# Sheet1.net
KiCad netlist of a schematic drawn in Altium Designer
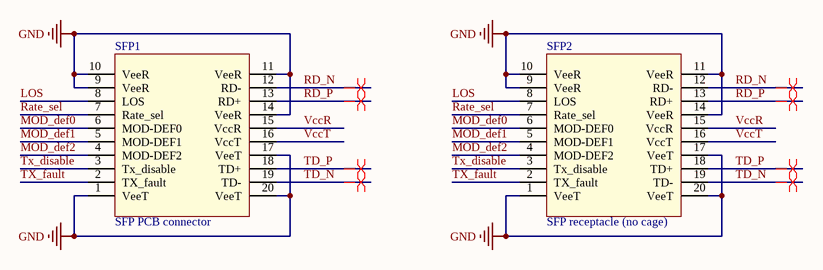
[diagram p0: Sheet1.SchDoc]

(export (version "E")
  (design (tool "Eeschema 10.0.6"))
  (components
    (comp (ref "SFP1")
      (value "SFP PCB connector")
      (footprint "SFP pcb con solder")
      (libsource (lib "SFPextension") (part "SFP PCB connector"))
    )
    (comp (ref "SFP2")
      (value "SFP receptacle (no cage)")
      (footprint "SFP receptacle (no cage)")
      (libsource (lib "SFPextension") (part "SFP receptacle (no cage)"))
    )
  )
  (nets
    (net (code "1") (name "/LOS") (class "Default")
      (node (ref "SFP1") (pin "8") (pinfunction "LOS_8") (pintype "power_in"))
      (node (ref "SFP2") (pin "8") (pinfunction "LOS_8") (pintype "power_in"))
    )
    (net (code "2") (name "/MOD_def0") (class "Default")
      (node (ref "SFP1") (pin "6") (pinfunction "MOD-DEF0_6") (pintype "power_in"))
      (node (ref "SFP2") (pin "6") (pinfunction "MOD-DEF0_6") (pintype "power_in"))
    )
    (net (code "3") (name "/MOD_def1") (class "Default")
      (node (ref "SFP1") (pin "5") (pinfunction "MOD-DEF1_5") (pintype "power_in"))
      (node (ref "SFP2") (pin "5") (pinfunction "MOD-DEF1_5") (pintype "power_in"))
    )
    (net (code "4") (name "/MOD_def2") (class "Default")
      (node (ref "SFP1") (pin "4") (pinfunction "MOD-DEF2_4") (pintype "power_in"))
      (node (ref "SFP2") (pin "4") (pinfunction "MOD-DEF2_4") (pintype "power_in"))
    )
    (net (code "5") (name "/RD_N") (class "Default")
      (node (ref "SFP1") (pin "12") (pinfunction "RD-_12") (pintype "power_in"))
      (node (ref "SFP2") (pin "12") (pinfunction "RD-_12") (pintype "power_in"))
    )
    (net (code "6") (name "/RD_P") (class "Default")
      (node (ref "SFP1") (pin "13") (pinfunction "RD+_13") (pintype "power_in"))
      (node (ref "SFP2") (pin "13") (pinfunction "RD+_13") (pintype "power_in"))
    )
    (net (code "7") (name "/Rate_sel") (class "Default")
      (node (ref "SFP1") (pin "7") (pinfunction "Rate_sel_7") (pintype "power_in"))
      (node (ref "SFP2") (pin "7") (pinfunction "Rate_sel_7") (pintype "power_in"))
    )
    (net (code "8") (name "/TD_N") (class "Default")
      (node (ref "SFP1") (pin "19") (pinfunction "TD-_19") (pintype "power_in"))
      (node (ref "SFP2") (pin "19") (pinfunction "TD-_19") (pintype "power_in"))
    )
    (net (code "9") (name "/TD_P") (class "Default")
      (node (ref "SFP1") (pin "18") (pinfunction "TD+_18") (pintype "power_in"))
      (node (ref "SFP2") (pin "18") (pinfunction "TD+_18") (pintype "power_in"))
    )
    (net (code "10") (name "/TX_fault") (class "Default")
      (node (ref "SFP1") (pin "2") (pinfunction "TX_fault_2") (pintype "power_in"))
      (node (ref "SFP2") (pin "2") (pinfunction "TX_fault_2") (pintype "power_in"))
    )
    (net (code "11") (name "/Tx_disable") (class "Default")
      (node (ref "SFP1") (pin "3") (pinfunction "Tx_disable_3") (pintype "power_in"))
      (node (ref "SFP2") (pin "3") (pinfunction "Tx_disable_3") (pintype "power_in"))
    )
    (net (code "12") (name "/VccR") (class "Default")
      (node (ref "SFP1") (pin "15") (pinfunction "VccR_15") (pintype "power_in"))
      (node (ref "SFP2") (pin "15") (pinfunction "VccR_15") (pintype "power_in"))
    )
    (net (code "13") (name "/VccT") (class "Default")
      (node (ref "SFP1") (pin "16") (pinfunction "VccT_16") (pintype "power_in"))
      (node (ref "SFP2") (pin "16") (pinfunction "VccT_16") (pintype "power_in"))
    )
    (net (code "14") (name "GND") (class "Default")
      (node (ref "SFP1") (pin "1") (pinfunction "VeeT_1") (pintype "power_in"))
      (node (ref "SFP1") (pin "10") (pinfunction "VeeR_10") (pintype "power_in"))
      (node (ref "SFP1") (pin "11") (pinfunction "VeeR_11") (pintype "power_in"))
      (node (ref "SFP1") (pin "14") (pinfunction "VeeR_14") (pintype "power_in"))
      (node (ref "SFP1") (pin "17") (pinfunction "VeeT_17") (pintype "power_in"))
      (node (ref "SFP1") (pin "20") (pinfunction "VeeT_20") (pintype "power_in"))
      (node (ref "SFP1") (pin "9") (pinfunction "VeeR_9") (pintype "power_in"))
      (node (ref "SFP2") (pin "1") (pinfunction "VeeT_1") (pintype "power_in"))
      (node (ref "SFP2") (pin "10") (pinfunction "VeeR_10") (pintype "power_in"))
      (node (ref "SFP2") (pin "11") (pinfunction "VeeR_11") (pintype "power_in"))
      (node (ref "SFP2") (pin "14") (pinfunction "VeeR_14") (pintype "power_in"))
      (node (ref "SFP2") (pin "17") (pinfunction "VeeT_17") (pintype "power_in"))
      (node (ref "SFP2") (pin "20") (pinfunction "VeeT_20") (pintype "power_in"))
      (node (ref "SFP2") (pin "9") (pinfunction "VeeR_9") (pintype "power_in"))
    )
  )
)
